# Motor_Controller.net
KiCad netlist of a schematic drawn in Altium Designer
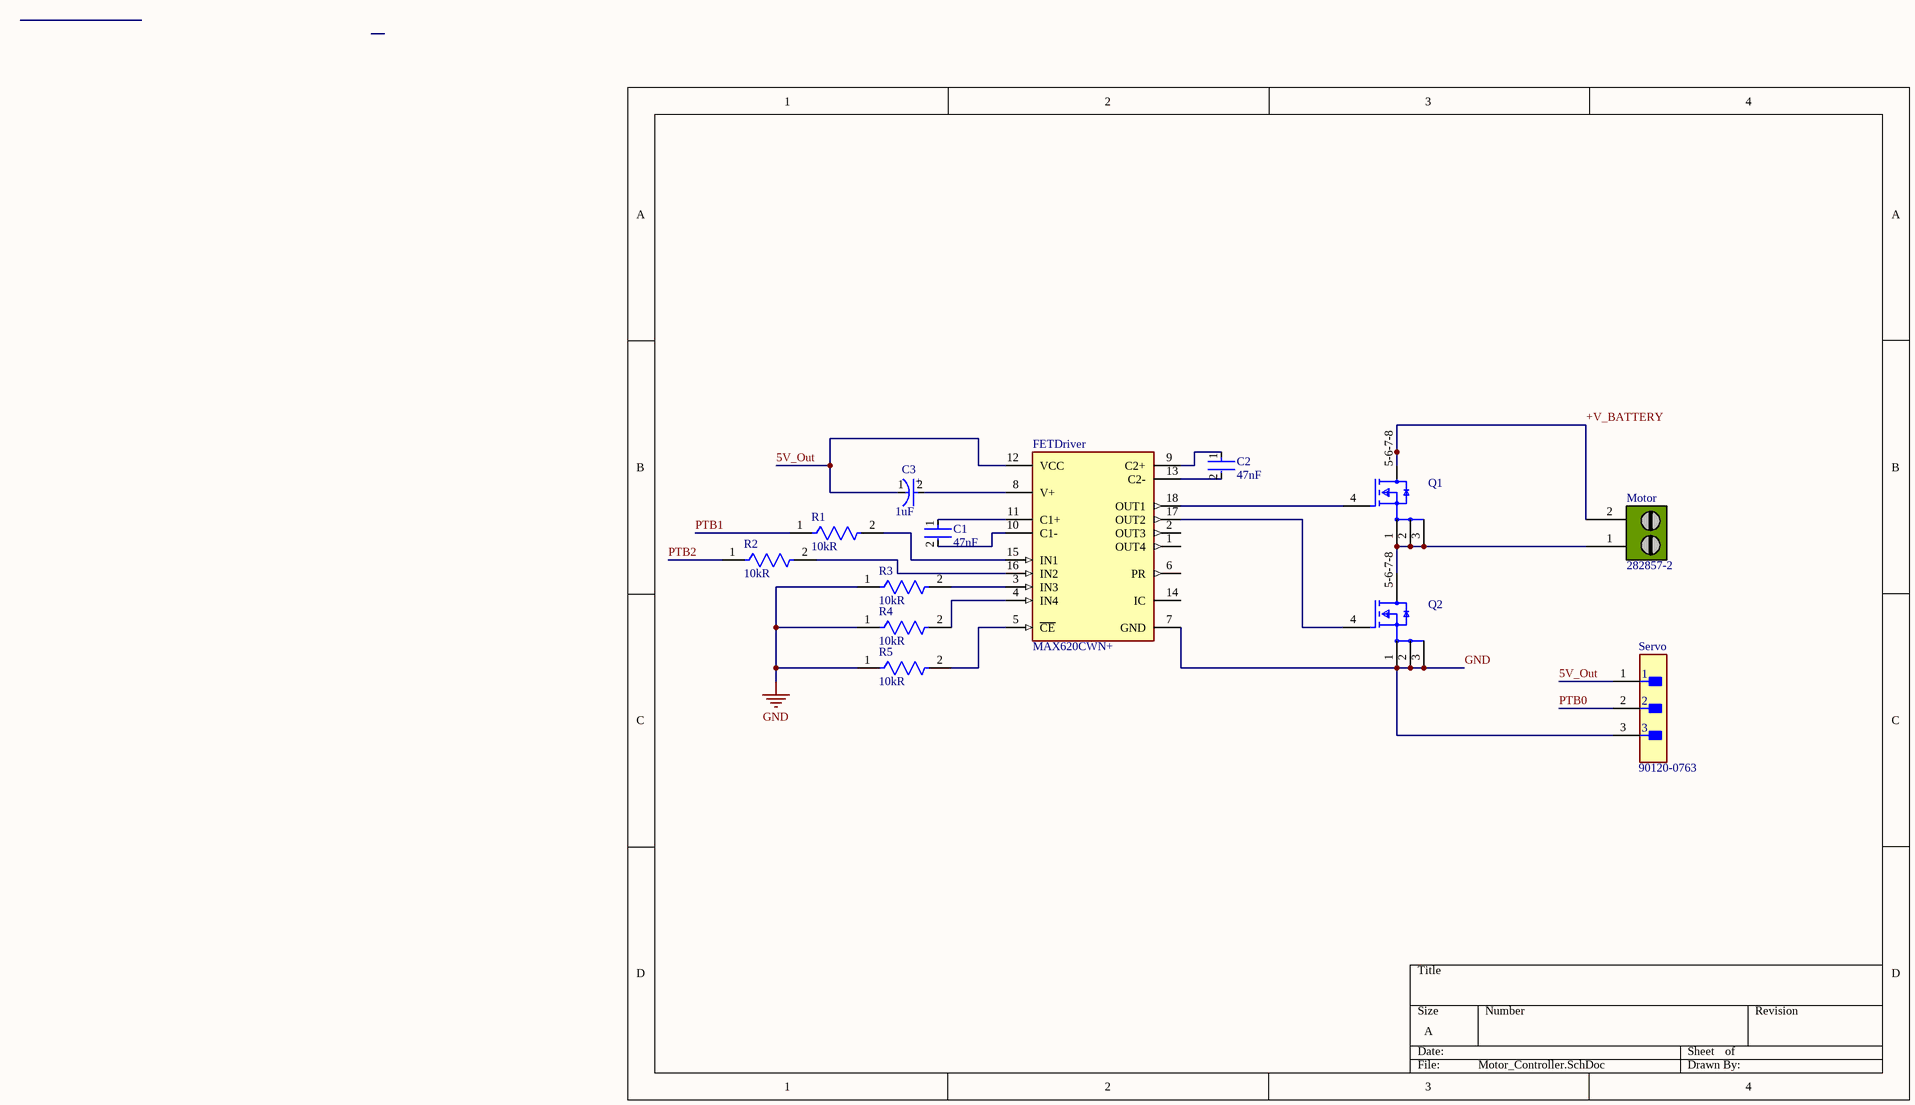
[diagram p0: Motor_Controller.SchDoc]

(export (version "E")
  (design (tool "Eeschema 10.0.6"))
  (components
    (comp (ref "C1")
      (value "08055C473JAT2A")
      (footprint "FP-0805-L_2_01_0_2-W_1_25-IPC_B")
      (description "General Purpose Ceramic Capacitor, 0805, 47nF, 5%, X7R, 0.15, 50V")
      (fields
        (field (name "VOLTAGE") "50V")
        (field (name "CAPACITANCE") "47nF")
        (field (name "TOLERANCE") "10%")
      )
      (libsource (lib "Altium Content Vault") (part "02cd4be3c70576c341d710602a673aa"))
    )
    (comp (ref "C2")
      (value "08055C473JAT2A")
      (footprint "FP-0805-L_2_01_0_2-W_1_25-IPC_B")
      (description "General Purpose Ceramic Capacitor, 0805, 47nF, 5%, X7R, 0.15, 50V")
      (fields
        (field (name "VOLTAGE") "50V")
        (field (name "CAPACITANCE") "47nF")
        (field (name "TOLERANCE") "10%")
      )
      (libsource (lib "Altium Content Vault") (part "02cd4be3c70576c341d710602a673aa"))
    )
    (comp (ref "C3")
      (value "T491A105K025AT")
      (footprint "FP-T491A105K025AT-MFG")
      (description "CAP TANT 1UF 10% 25V 1206")
      (fields
        (field (name "CAPACITANCE") "1uF")
        (field (name "TOLERANCE") "20%")
        (field (name "VOLTAGE") "25V")
      )
      (libsource (lib "Altium Content Vault") (part "a00bbbee19879c290e62620ae7e47b1"))
    )
    (comp (ref "FETDriver")
      (value "MAX620CWN+")
      (footprint "FP-W18-1-MFG")
      (description "IC GATE DRVR HIGH-SIDE 18SOIC")
      (libsource (lib "Altium Content Vault") (part "c2ec74dac6dc176bf3e825ca6eb1ba2"))
    )
    (comp (ref "Motor")
      (value "282857-2")
      (footprint "282857-2")
      (description "TERM BLOCK 2POS SIDE ENT 5.08MM")
      (fields (field (name "MANUFACTURER") "TE Connectivity") (field (name "VOLTAGE") "300V"))
      (libsource (lib "eConnector") (part "282857-2"))
    )
    (comp (ref "Q1")
      (value "CSD17306Q5A")
      (footprint "FP-DQJ0008A-MFG")
      (description "MOSFET N-CH 30V 24A/100A 8VSON")
      (libsource (lib "Altium Content Vault") (part "7382af88e928fdc71488234cfaaf11c"))
    )
    (comp (ref "Q2")
      (value "CSD17306Q5A")
      (footprint "FP-DQJ0008A-MFG")
      (description "MOSFET N-CH 30V 24A/100A 8VSON")
      (libsource (lib "Altium Content Vault") (part "7382af88e928fdc71488234cfaaf11c"))
    )
    (comp (ref "R1")
      (value "CR0805-JW-103ELF")
      (footprint "FP-CR0805-IPC_B")
      (description "Thick Film Chip Resistors 0805 10kΩ 0.125W 5% 200ppm/°C")
      (fields (field (name "RESISTANCE") "10kR") (field (name "TOLERANCE") "5%"))
      (libsource (lib "Altium Content Vault") (part "1029c3af85768c4190bb7ad29bc67b5"))
    )
    (comp (ref "R2")
      (value "CR0805-JW-103ELF")
      (footprint "FP-CR0805-IPC_B")
      (description "Thick Film Chip Resistors 0805 10kΩ 0.125W 5% 200ppm/°C")
      (fields (field (name "RESISTANCE") "10kR") (field (name "TOLERANCE") "5%"))
      (libsource (lib "Altium Content Vault") (part "1029c3af85768c4190bb7ad29bc67b5"))
    )
    (comp (ref "R3")
      (value "CR0805-JW-103ELF")
      (footprint "FP-CR0805-IPC_B")
      (description "Thick Film Chip Resistors 0805 10kΩ 0.125W 5% 200ppm/°C")
      (fields (field (name "RESISTANCE") "10kR") (field (name "TOLERANCE") "5%"))
      (libsource (lib "Altium Content Vault") (part "1029c3af85768c4190bb7ad29bc67b5"))
    )
    (comp (ref "R4")
      (value "CR0805-JW-103ELF")
      (footprint "FP-CR0805-IPC_B")
      (description "Thick Film Chip Resistors 0805 10kΩ 0.125W 5% 200ppm/°C")
      (fields (field (name "RESISTANCE") "10kR") (field (name "TOLERANCE") "5%"))
      (libsource (lib "Altium Content Vault") (part "1029c3af85768c4190bb7ad29bc67b5"))
    )
    (comp (ref "R5")
      (value "CR0805-JW-103ELF")
      (footprint "FP-CR0805-IPC_B")
      (description "Thick Film Chip Resistors 0805 10kΩ 0.125W 5% 200ppm/°C")
      (fields (field (name "RESISTANCE") "10kR") (field (name "TOLERANCE") "5%"))
      (libsource (lib "Altium Content Vault") (part "1029c3af85768c4190bb7ad29bc67b5"))
    )
    (comp (ref "Servo")
      (value "90120-0763")
      (footprint "FP-90120-0763-MFG")
      (description "CONN HEADER VERT 3POS 2.54MM")
      (fields
        (field (name "MANUFACTURER") "Molex")
        (field (name "OCTOPART") "https://octopart.com/90120-0763-molex-655433")
      )
      (libsource (lib "Altium Content Vault") (part "0d3f023dd272f625e17a2be33dea85f"))
    )
  )
  (nets
    (net (code "1") (name "/+V_BATTERY") (class "Default")
      (node (ref "Motor") (pin "2") (pinfunction "2_2") (pintype "passive"))
      (node (ref "Q1") (pin "5-6-7-8") (pinfunction "D_5-6-7-8") (pintype "passive"))
    )
    (net (code "2") (name "/5V_Out") (class "Default")
      (node (ref "C3") (pin "1") (pinfunction "C_1") (pintype "passive"))
      (node (ref "FETDriver") (pin "12") (pinfunction "VCC_12") (pintype "power_in"))
      (node (ref "Servo") (pin "1") (pinfunction "1_1") (pintype "passive"))
    )
    (net (code "3") (name "/PTB0") (class "Default")
      (node (ref "Servo") (pin "2") (pinfunction "2_2") (pintype "passive"))
    )
    (net (code "4") (name "/PTB1") (class "Default")
      (node (ref "R1") (pin "1") (pinfunction "1_1") (pintype "passive"))
    )
    (net (code "5") (name "/PTB2") (class "Default")
      (node (ref "R2") (pin "1") (pinfunction "1_1") (pintype "passive"))
    )
    (net (code "6") (name "GND") (class "Default")
      (node (ref "FETDriver") (pin "7") (pinfunction "GND_7") (pintype "power_in"))
      (node (ref "Q2") (pin "1") (pinfunction "S_1") (pintype "passive"))
      (node (ref "Q2") (pin "2") (pinfunction "S_2") (pintype "passive"))
      (node (ref "Q2") (pin "3") (pinfunction "S_3") (pintype "passive"))
      (node (ref "R3") (pin "1") (pinfunction "1_1") (pintype "passive"))
      (node (ref "R4") (pin "1") (pinfunction "1_1") (pintype "passive"))
      (node (ref "R5") (pin "1") (pinfunction "1_1") (pintype "passive"))
      (node (ref "Servo") (pin "3") (pinfunction "3_3") (pintype "passive"))
    )
    (net (code "7") (name "Net-(C3-A)") (class "Default")
      (node (ref "C3") (pin "2") (pinfunction "A_2") (pintype "passive"))
      (node (ref "FETDriver") (pin "8") (pinfunction "V+_8") (pintype "power_in"))
    )
    (net (code "8") (name "Net-(FETDriver-C1+)") (class "Default")
      (node (ref "C1") (pin "1") (pinfunction "1_1") (pintype "passive"))
      (node (ref "FETDriver") (pin "11") (pinfunction "C1+_11") (pintype "passive"))
    )
    (net (code "9") (name "Net-(FETDriver-C1-)") (class "Default")
      (node (ref "C1") (pin "2") (pinfunction "2_2") (pintype "passive"))
      (node (ref "FETDriver") (pin "10") (pinfunction "C1-_10") (pintype "passive"))
    )
    (net (code "10") (name "Net-(FETDriver-C2+)") (class "Default")
      (node (ref "C2") (pin "1") (pinfunction "1_1") (pintype "passive"))
      (node (ref "FETDriver") (pin "9") (pinfunction "C2+_9") (pintype "passive"))
    )
    (net (code "11") (name "Net-(FETDriver-C2-)") (class "Default")
      (node (ref "C2") (pin "2") (pinfunction "2_2") (pintype "passive"))
      (node (ref "FETDriver") (pin "13") (pinfunction "C2-_13") (pintype "passive"))
    )
    (net (code "12") (name "Net-(FETDriver-IN1)") (class "Default")
      (node (ref "FETDriver") (pin "15") (pinfunction "IN1_15") (pintype "input"))
      (node (ref "R1") (pin "2") (pinfunction "2_2") (pintype "passive"))
    )
    (net (code "13") (name "Net-(FETDriver-IN2)") (class "Default")
      (node (ref "FETDriver") (pin "16") (pinfunction "IN2_16") (pintype "input"))
      (node (ref "R2") (pin "2") (pinfunction "2_2") (pintype "passive"))
    )
    (net (code "14") (name "Net-(FETDriver-IN3)") (class "Default")
      (node (ref "FETDriver") (pin "3") (pinfunction "IN3_3") (pintype "input"))
      (node (ref "R3") (pin "2") (pinfunction "2_2") (pintype "passive"))
    )
    (net (code "15") (name "Net-(FETDriver-IN4)") (class "Default")
      (node (ref "FETDriver") (pin "4") (pinfunction "IN4_4") (pintype "input"))
      (node (ref "R4") (pin "2") (pinfunction "2_2") (pintype "passive"))
    )
    (net (code "16") (name "Net-(FETDriver-OUT1)") (class "Default")
      (node (ref "FETDriver") (pin "18") (pinfunction "OUT1_18") (pintype "output"))
      (node (ref "Q1") (pin "4") (pinfunction "G_4") (pintype "passive"))
    )
    (net (code "17") (name "Net-(FETDriver-OUT2)") (class "Default")
      (node (ref "FETDriver") (pin "17") (pinfunction "OUT2_17") (pintype "output"))
      (node (ref "Q2") (pin "4") (pinfunction "G_4") (pintype "passive"))
    )
    (net (code "18") (name "Net-(FETDriver-~{CE})") (class "Default")
      (node (ref "FETDriver") (pin "5") (pinfunction "~{CE}_5") (pintype "input"))
      (node (ref "R5") (pin "2") (pinfunction "2_2") (pintype "passive"))
    )
    (net (code "19") (name "Net-(Q2-D)") (class "Default")
      (node (ref "Motor") (pin "1") (pinfunction "1_1") (pintype "passive"))
      (node (ref "Q1") (pin "1") (pinfunction "S_1") (pintype "passive"))
      (node (ref "Q1") (pin "2") (pinfunction "S_2") (pintype "passive"))
      (node (ref "Q1") (pin "3") (pinfunction "S_3") (pintype "passive"))
      (node (ref "Q2") (pin "5-6-7-8") (pinfunction "D_5-6-7-8") (pintype "passive"))
    )
    (net (code "20") (name "unconnected-(FETDriver-IC-Pad14)") (class "Default")
      (node (ref "FETDriver") (pin "14") (pinfunction "IC_14") (pintype "passive"))
    )
    (net (code "21") (name "unconnected-(FETDriver-OUT3-Pad2)") (class "Default")
      (node (ref "FETDriver") (pin "2") (pinfunction "OUT3_2") (pintype "output"))
    )
    (net (code "22") (name "unconnected-(FETDriver-OUT4-Pad1)") (class "Default")
      (node (ref "FETDriver") (pin "1") (pinfunction "OUT4_1") (pintype "output"))
    )
    (net (code "23") (name "unconnected-(FETDriver-PR-Pad6)") (class "Default")
      (node (ref "FETDriver") (pin "6") (pinfunction "PR_6") (pintype "output"))
    )
  )
)
